# NixieDriverPower.net
KiCad netlist of a schematic drawn in EAGLE
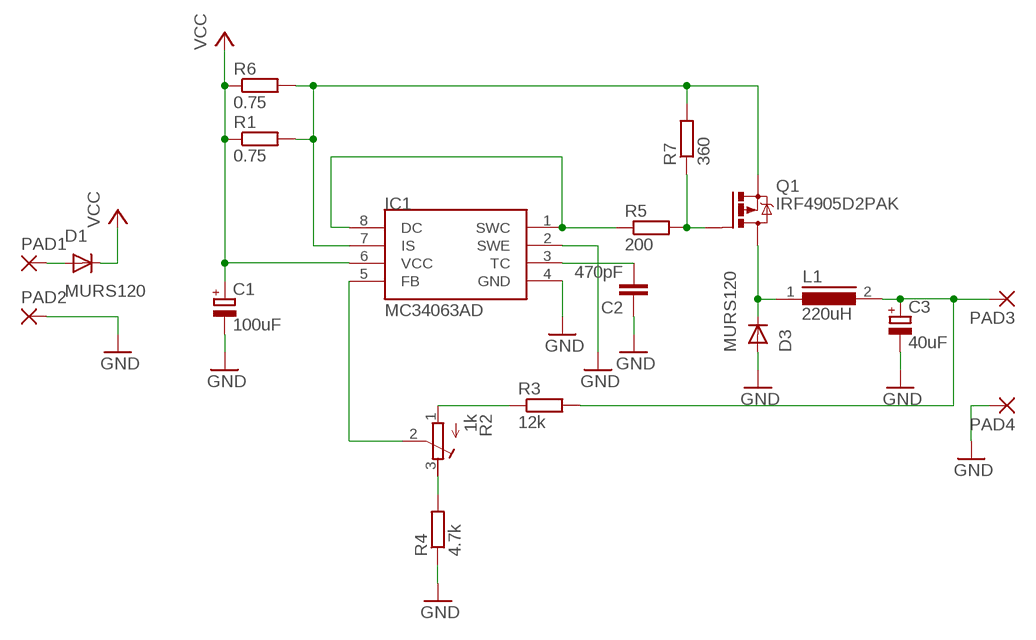
[diagram p0: schematic, sheet 1]

(export (version "E")
  (design (tool "Eeschema 10.0.6"))
  (components
    (comp (ref "C1")
      (value "100uF")
      (footprint "eagle-import:D_7343-31R")
      (libsource (lib "eagle-import") (part "CPOL-EUD/7343-31R"))
    )
    (comp (ref "C2")
      (value "470pF")
      (footprint "eagle-import:C1206K")
      (libsource (lib "eagle-import") (part "C-EUC1206K"))
    )
    (comp (ref "C3")
      (value "40uF")
      (footprint "eagle-import:C_6032-28R")
      (libsource (lib "eagle-import") (part "CPOL-EUC/6032-28R"))
    )
    (comp (ref "D1")
      (value "MURS120")
      (footprint "eagle-import:DO214AA")
      (libsource (lib "eagle-import") (part "DIODE-DO214AA"))
    )
    (comp (ref "D3")
      (value "MURS120")
      (footprint "eagle-import:DO214AA")
      (libsource (lib "eagle-import") (part "DIODE-DO214AA"))
    )
    (comp (ref "IC1")
      (value "MC34063AD")
      (footprint "eagle-import:SOIC8")
      (libsource (lib "eagle-import") (part "MC34063AD"))
    )
    (comp (ref "L1")
      (value "220uH")
      (footprint "eagle-import:DR125")
      (libsource (lib "eagle-import") (part "DR125"))
    )
    (comp (ref "PAD1")
      (value "SMD5")
      (footprint "eagle-import:SMD2,54-5,08")
      (libsource (lib "eagle-import") (part "SMD5"))
    )
    (comp (ref "PAD2")
      (value "SMD5")
      (footprint "eagle-import:SMD2,54-5,08")
      (libsource (lib "eagle-import") (part "SMD5"))
    )
    (comp (ref "PAD3")
      (value "SMD5")
      (footprint "eagle-import:SMD2,54-5,08")
      (libsource (lib "eagle-import") (part "SMD5"))
    )
    (comp (ref "PAD4")
      (value "SMD5")
      (footprint "eagle-import:SMD2,54-5,08")
      (libsource (lib "eagle-import") (part "SMD5"))
    )
    (comp (ref "Q1")
      (value "IRF4905D2PAK")
      (footprint "eagle-import:D2PAK")
      (libsource (lib "eagle-import") (part "IRF4905D2PAK"))
    )
    (comp (ref "R1")
      (value "0.75")
      (footprint "eagle-import:R1206")
      (libsource (lib "eagle-import") (part "R-EU_R1206"))
    )
    (comp (ref "R2")
      (value "1k")
      (footprint "eagle-import:RTRIM4G_J")
      (libsource (lib "eagle-import") (part "R-TRIMM4G/J"))
    )
    (comp (ref "R3")
      (value "12k")
      (footprint "eagle-import:R1206")
      (libsource (lib "eagle-import") (part "R-EU_R1206"))
    )
    (comp (ref "R4")
      (value "4.7k")
      (footprint "eagle-import:R1206")
      (libsource (lib "eagle-import") (part "R-EU_R1206"))
    )
    (comp (ref "R5")
      (value "200")
      (footprint "eagle-import:R1206")
      (libsource (lib "eagle-import") (part "R-EU_R1206"))
    )
    (comp (ref "R6")
      (value "0.75")
      (footprint "eagle-import:R1206")
      (libsource (lib "eagle-import") (part "R-EU_R1206"))
    )
    (comp (ref "R7")
      (value "360")
      (footprint "eagle-import:R1206")
      (libsource (lib "eagle-import") (part "R-EU_R1206"))
    )
  )
  (nets
    (net (code "1") (name "GND") (class "Default")
      (node (ref "C1") (pin "-") (pinfunction "-_-") (pintype "passive"))
      (node (ref "C2") (pin "1") (pinfunction "1_1") (pintype "passive"))
      (node (ref "C3") (pin "-") (pinfunction "-_-") (pintype "passive"))
      (node (ref "D3") (pin "A") (pinfunction "A_A") (pintype "passive"))
      (node (ref "IC1") (pin "2") (pinfunction "SWE_2") (pintype "passive"))
      (node (ref "IC1") (pin "4") (pinfunction "GND_4") (pintype "passive"))
      (node (ref "PAD2") (pin "1") (pinfunction "P_1") (pintype "passive"))
      (node (ref "PAD4") (pin "1") (pinfunction "P_1") (pintype "passive"))
      (node (ref "R4") (pin "1") (pinfunction "1_1") (pintype "passive"))
    )
    (net (code "2") (name "Net-(IC1-DC)") (class "Default")
      (node (ref "IC1") (pin "1") (pinfunction "SWC_1") (pintype "passive"))
      (node (ref "IC1") (pin "8") (pinfunction "DC_8") (pintype "passive"))
      (node (ref "R5") (pin "1") (pinfunction "1_1") (pintype "passive"))
    )
    (net (code "3") (name "Net-(IC1-FB)") (class "Default")
      (node (ref "IC1") (pin "5") (pinfunction "FB_5") (pintype "passive"))
      (node (ref "R2") (pin "2") (pinfunction "S_2") (pintype "passive"))
    )
    (net (code "4") (name "Net-(IC1-IS)") (class "Default")
      (node (ref "IC1") (pin "7") (pinfunction "IS_7") (pintype "passive"))
      (node (ref "Q1") (pin "3") (pinfunction "S_3") (pintype "passive"))
      (node (ref "R1") (pin "2") (pinfunction "2_2") (pintype "passive"))
      (node (ref "R6") (pin "2") (pinfunction "2_2") (pintype "passive"))
      (node (ref "R7") (pin "2") (pinfunction "2_2") (pintype "passive"))
    )
    (net (code "5") (name "Net-(IC1-TC)") (class "Default")
      (node (ref "C2") (pin "2") (pinfunction "2_2") (pintype "passive"))
      (node (ref "IC1") (pin "3") (pinfunction "TC_3") (pintype "passive"))
    )
    (net (code "6") (name "Net-(PAD1-P)") (class "Default")
      (node (ref "D1") (pin "A") (pinfunction "A_A") (pintype "passive"))
      (node (ref "PAD1") (pin "1") (pinfunction "P_1") (pintype "passive"))
    )
    (net (code "7") (name "Net-(PAD3-P)") (class "Default")
      (node (ref "C3") (pin "+") (pinfunction "+_+") (pintype "passive"))
      (node (ref "L1") (pin "2") (pinfunction "2_2") (pintype "passive"))
      (node (ref "PAD3") (pin "1") (pinfunction "P_1") (pintype "passive"))
      (node (ref "R3") (pin "2") (pinfunction "2_2") (pintype "passive"))
    )
    (net (code "8") (name "Net-(Q1-D)") (class "Default")
      (node (ref "D3") (pin "C") (pinfunction "C_C") (pintype "passive"))
      (node (ref "L1") (pin "1") (pinfunction "1_1") (pintype "passive"))
      (node (ref "Q1") (pin "4") (pinfunction "D_4") (pintype "passive"))
    )
    (net (code "9") (name "Net-(Q1-G)") (class "Default")
      (node (ref "Q1") (pin "1") (pinfunction "G_1") (pintype "passive"))
      (node (ref "R5") (pin "2") (pinfunction "2_2") (pintype "passive"))
      (node (ref "R7") (pin "1") (pinfunction "1_1") (pintype "passive"))
    )
    (net (code "10") (name "Net-(R2-A)") (class "Default")
      (node (ref "R2") (pin "1") (pinfunction "A_1") (pintype "passive"))
      (node (ref "R3") (pin "1") (pinfunction "1_1") (pintype "passive"))
    )
    (net (code "11") (name "Net-(R2-E)") (class "Default")
      (node (ref "R2") (pin "3") (pinfunction "E_3") (pintype "passive"))
      (node (ref "R4") (pin "2") (pinfunction "2_2") (pintype "passive"))
    )
    (net (code "12") (name "VCC") (class "Default")
      (node (ref "C1") (pin "+") (pinfunction "+_+") (pintype "passive"))
      (node (ref "D1") (pin "C") (pinfunction "C_C") (pintype "passive"))
      (node (ref "IC1") (pin "6") (pinfunction "VCC_6") (pintype "passive"))
      (node (ref "R1") (pin "1") (pinfunction "1_1") (pintype "passive"))
      (node (ref "R6") (pin "1") (pinfunction "1_1") (pintype "passive"))
    )
  )
)
